# Microbrute_Output_Board.net
KiCad netlist of a schematic drawn in EAGLE
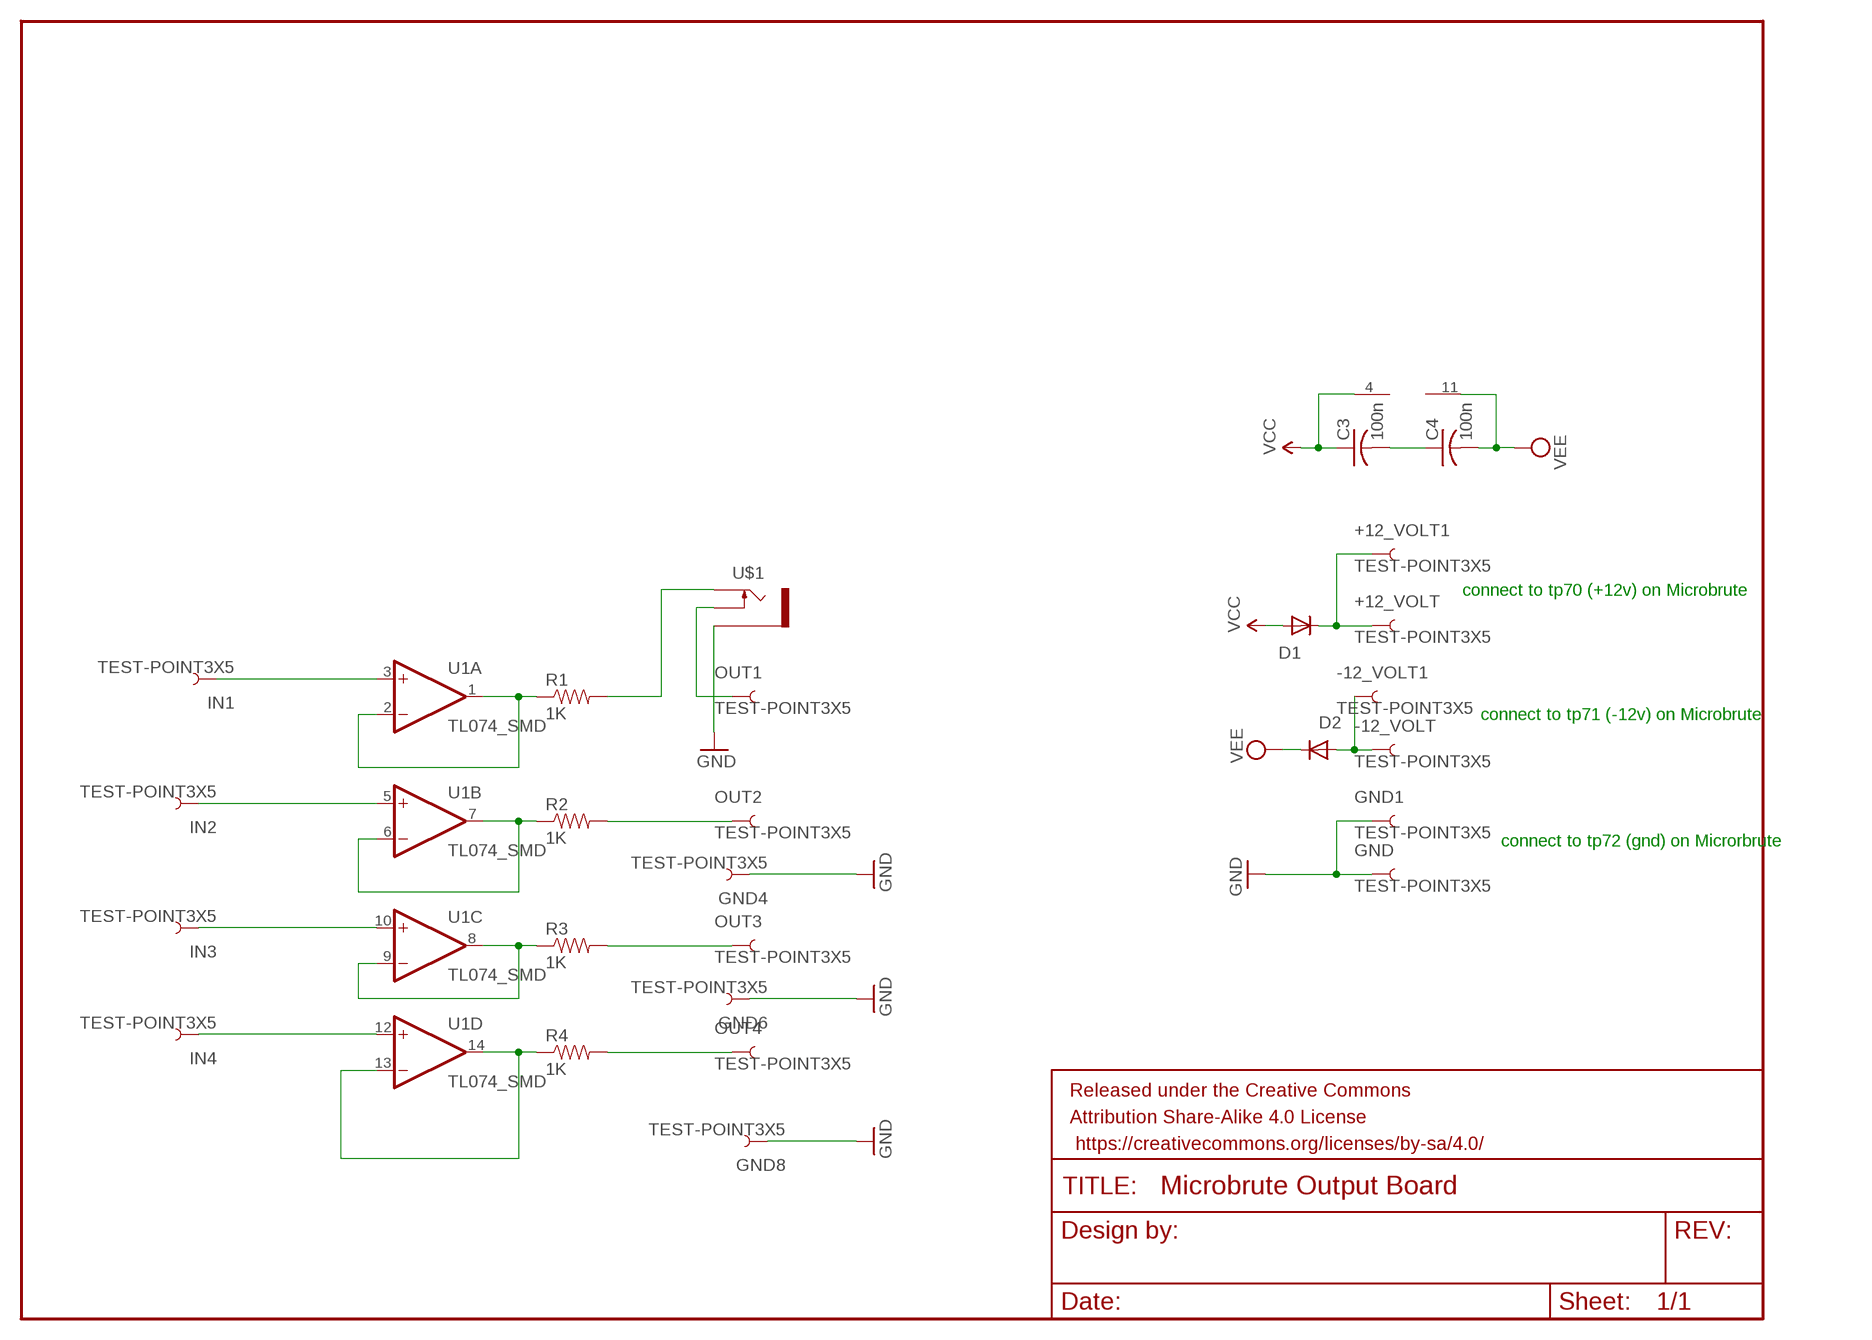
[diagram p0: schematic, sheet 1]

(export (version "E")
  (design (tool "Eeschema 10.0.6"))
  (components
    (comp (ref "+12_VOLT")
      (value "TEST-POINT3X5")
      (footprint "eagle-import:PAD.03X.05")
      (libsource (lib "eagle-import") (part "TEST-POINT3X5"))
    )
    (comp (ref "+12_VOLT1")
      (value "TEST-POINT3X5")
      (footprint "eagle-import:PAD.03X.05")
      (libsource (lib "eagle-import") (part "TEST-POINT3X5"))
    )
    (comp (ref "-12_VOLT")
      (value "TEST-POINT3X5")
      (footprint "eagle-import:PAD.03X.05")
      (libsource (lib "eagle-import") (part "TEST-POINT3X5"))
    )
    (comp (ref "-12_VOLT1")
      (value "TEST-POINT3X5")
      (footprint "eagle-import:PAD.03X.05")
      (libsource (lib "eagle-import") (part "TEST-POINT3X5"))
    )
    (comp (ref "C3")
      (value "100n")
      (footprint "eagle-import:C0603")
      (libsource (lib "eagle-import") (part "C-USC0603"))
    )
    (comp (ref "C4")
      (value "100n")
      (footprint "eagle-import:C0603")
      (libsource (lib "eagle-import") (part "C-USC0603"))
    )
    (comp (ref "D1")
      (value "1N5819HW")
      (footprint "eagle-import:SOD123")
      (libsource (lib "eagle-import") (part "DIODE-SOD123"))
    )
    (comp (ref "D2")
      (value "1N5819HW")
      (footprint "eagle-import:SOD123")
      (libsource (lib "eagle-import") (part "DIODE-SOD123"))
    )
    (comp (ref "FRAME1")
      (value "FRAME-LETTER")
      (footprint "eagle-import:CREATIVE_COMMONS")
      (libsource (lib "eagle-import") (part "FRAME-LETTER"))
    )
    (comp (ref "GND")
      (value "TEST-POINT3X5")
      (footprint "eagle-import:PAD.03X.05")
      (libsource (lib "eagle-import") (part "TEST-POINT3X5"))
    )
    (comp (ref "GND1")
      (value "TEST-POINT3X5")
      (footprint "eagle-import:PAD.03X.05")
      (libsource (lib "eagle-import") (part "TEST-POINT3X5"))
    )
    (comp (ref "GND4")
      (value "TEST-POINT3X5")
      (footprint "eagle-import:PAD.03X.05")
      (libsource (lib "eagle-import") (part "TEST-POINT3X5"))
    )
    (comp (ref "GND6")
      (value "TEST-POINT3X5")
      (footprint "eagle-import:PAD.03X.05")
      (libsource (lib "eagle-import") (part "TEST-POINT3X5"))
    )
    (comp (ref "GND8")
      (value "TEST-POINT3X5")
      (footprint "eagle-import:PAD.03X.05")
      (libsource (lib "eagle-import") (part "TEST-POINT3X5"))
    )
    (comp (ref "IN1")
      (value "TEST-POINT3X5")
      (footprint "eagle-import:PAD.03X.05")
      (libsource (lib "eagle-import") (part "TEST-POINT3X5"))
    )
    (comp (ref "IN2")
      (value "TEST-POINT3X5")
      (footprint "eagle-import:PAD.03X.05")
      (libsource (lib "eagle-import") (part "TEST-POINT3X5"))
    )
    (comp (ref "IN3")
      (value "TEST-POINT3X5")
      (footprint "eagle-import:PAD.03X.05")
      (libsource (lib "eagle-import") (part "TEST-POINT3X5"))
    )
    (comp (ref "IN4")
      (value "TEST-POINT3X5")
      (footprint "eagle-import:PAD.03X.05")
      (libsource (lib "eagle-import") (part "TEST-POINT3X5"))
    )
    (comp (ref "OUT1")
      (value "TEST-POINT3X5")
      (footprint "eagle-import:PAD.03X.05")
      (libsource (lib "eagle-import") (part "TEST-POINT3X5"))
    )
    (comp (ref "OUT2")
      (value "TEST-POINT3X5")
      (footprint "eagle-import:PAD.03X.05")
      (libsource (lib "eagle-import") (part "TEST-POINT3X5"))
    )
    (comp (ref "OUT3")
      (value "TEST-POINT3X5")
      (footprint "eagle-import:PAD.03X.05")
      (libsource (lib "eagle-import") (part "TEST-POINT3X5"))
    )
    (comp (ref "OUT4")
      (value "TEST-POINT3X5")
      (footprint "eagle-import:PAD.03X.05")
      (libsource (lib "eagle-import") (part "TEST-POINT3X5"))
    )
    (comp (ref "R1")
      (value "1K")
      (footprint "eagle-import:0603-RES")
      (libsource (lib "eagle-import") (part "1KOHM-1/10W-1%(0603)"))
    )
    (comp (ref "R2")
      (value "1K")
      (footprint "eagle-import:0603-RES")
      (libsource (lib "eagle-import") (part "1KOHM-1/10W-1%(0603)"))
    )
    (comp (ref "R3")
      (value "1K")
      (footprint "eagle-import:0603-RES")
      (libsource (lib "eagle-import") (part "1KOHM-1/10W-1%(0603)"))
    )
    (comp (ref "R4")
      (value "1K")
      (footprint "eagle-import:0603-RES")
      (libsource (lib "eagle-import") (part "1KOHM-1/10W-1%(0603)"))
    )
    (comp (ref "U$1")
      (value "THONKICONNNEW")
      (footprint "eagle-import:WQP-PJ301M-12_JACK")
      (libsource (lib "eagle-import") (part "THONKICONNNEW"))
    )
    (comp (ref "U1")
      (value "TL074_SMD")
      (footprint "eagle-import:SO14")
      (libsource (lib "eagle-import") (part "TL074_SMD"))
    )
  )
  (nets
    (net (code "1") (name "GND") (class "Default")
      (node (ref "GND") (pin "P$1") (pinfunction "1_P$1") (pintype "bidirectional"))
      (node (ref "GND1") (pin "P$1") (pinfunction "1_P$1") (pintype "bidirectional"))
      (node (ref "GND4") (pin "P$1") (pinfunction "1_P$1") (pintype "bidirectional"))
      (node (ref "GND6") (pin "P$1") (pinfunction "1_P$1") (pintype "bidirectional"))
      (node (ref "GND8") (pin "P$1") (pinfunction "1_P$1") (pintype "bidirectional"))
      (node (ref "U$1") (pin "P$3_SLEEVE") (pinfunction "SLEEVE_P$3_SLEEVE") (pintype "passive"))
    )
    (net (code "2") (name "Net-(+12_VOLT-1)") (class "Default")
      (node (ref "+12_VOLT") (pin "P$1") (pinfunction "1_P$1") (pintype "bidirectional"))
      (node (ref "+12_VOLT1") (pin "P$1") (pinfunction "1_P$1") (pintype "bidirectional"))
      (node (ref "D1") (pin "C") (pinfunction "C_C") (pintype "passive"))
    )
    (net (code "3") (name "Net-(-12_VOLT-1)") (class "Default")
      (node (ref "-12_VOLT") (pin "P$1") (pinfunction "1_P$1") (pintype "bidirectional"))
      (node (ref "-12_VOLT1") (pin "P$1") (pinfunction "1_P$1") (pintype "bidirectional"))
      (node (ref "D2") (pin "A") (pinfunction "A_A") (pintype "passive"))
    )
    (net (code "4") (name "Net-(C3-Pad2)") (class "Default")
      (node (ref "C3") (pin "2") (pinfunction "2_2") (pintype "passive"))
      (node (ref "C4") (pin "1") (pinfunction "1_1") (pintype "passive"))
    )
    (net (code "5") (name "Net-(IN1-1)") (class "Default")
      (node (ref "IN1") (pin "P$1") (pinfunction "1_P$1") (pintype "bidirectional"))
      (node (ref "U1") (pin "3") (pinfunction "+IN_3") (pintype "input"))
    )
    (net (code "6") (name "Net-(IN2-1)") (class "Default")
      (node (ref "IN2") (pin "P$1") (pinfunction "1_P$1") (pintype "bidirectional"))
      (node (ref "U1") (pin "5") (pinfunction "+IN_5") (pintype "input"))
    )
    (net (code "7") (name "Net-(IN3-1)") (class "Default")
      (node (ref "IN3") (pin "P$1") (pinfunction "1_P$1") (pintype "bidirectional"))
      (node (ref "U1") (pin "10") (pinfunction "+IN_10") (pintype "input"))
    )
    (net (code "8") (name "Net-(IN4-1)") (class "Default")
      (node (ref "IN4") (pin "P$1") (pinfunction "1_P$1") (pintype "bidirectional"))
      (node (ref "U1") (pin "12") (pinfunction "+IN_12") (pintype "input"))
    )
    (net (code "9") (name "Net-(OUT1-1)") (class "Default")
      (node (ref "OUT1") (pin "P$1") (pinfunction "1_P$1") (pintype "bidirectional"))
      (node (ref "U$1") (pin "P$2_SWITCH") (pinfunction "SWITCH_P$2_SWITCH") (pintype "passive"))
    )
    (net (code "10") (name "Net-(OUT2-1)") (class "Default")
      (node (ref "OUT2") (pin "P$1") (pinfunction "1_P$1") (pintype "bidirectional"))
      (node (ref "R2") (pin "2") (pinfunction "2_2") (pintype "passive"))
    )
    (net (code "11") (name "Net-(OUT3-1)") (class "Default")
      (node (ref "OUT3") (pin "P$1") (pinfunction "1_P$1") (pintype "bidirectional"))
      (node (ref "R3") (pin "2") (pinfunction "2_2") (pintype "passive"))
    )
    (net (code "12") (name "Net-(OUT4-1)") (class "Default")
      (node (ref "OUT4") (pin "P$1") (pinfunction "1_P$1") (pintype "bidirectional"))
      (node (ref "R4") (pin "2") (pinfunction "2_2") (pintype "passive"))
    )
    (net (code "13") (name "Net-(U$1-TIP)") (class "Default")
      (node (ref "R1") (pin "2") (pinfunction "2_2") (pintype "passive"))
      (node (ref "U$1") (pin "P$1_TIP") (pinfunction "TIP_P$1_TIP") (pintype "passive"))
    )
    (net (code "14") (name "Net-(U1A--IN)") (class "Default")
      (node (ref "R1") (pin "1") (pinfunction "1_1") (pintype "passive"))
      (node (ref "U1") (pin "1") (pinfunction "OUT_1") (pintype "output"))
      (node (ref "U1") (pin "2") (pinfunction "-IN_2") (pintype "input"))
    )
    (net (code "15") (name "Net-(U1B--IN)") (class "Default")
      (node (ref "R2") (pin "1") (pinfunction "1_1") (pintype "passive"))
      (node (ref "U1") (pin "6") (pinfunction "-IN_6") (pintype "input"))
      (node (ref "U1") (pin "7") (pinfunction "OUT_7") (pintype "output"))
    )
    (net (code "16") (name "Net-(U1C--IN)") (class "Default")
      (node (ref "R3") (pin "1") (pinfunction "1_1") (pintype "passive"))
      (node (ref "U1") (pin "8") (pinfunction "OUT_8") (pintype "output"))
      (node (ref "U1") (pin "9") (pinfunction "-IN_9") (pintype "input"))
    )
    (net (code "17") (name "Net-(U1D--IN)") (class "Default")
      (node (ref "R4") (pin "1") (pinfunction "1_1") (pintype "passive"))
      (node (ref "U1") (pin "13") (pinfunction "-IN_13") (pintype "input"))
      (node (ref "U1") (pin "14") (pinfunction "OUT_14") (pintype "output"))
    )
    (net (code "18") (name "VCC") (class "Default")
      (node (ref "C3") (pin "1") (pinfunction "1_1") (pintype "passive"))
      (node (ref "D1") (pin "A") (pinfunction "A_A") (pintype "passive"))
      (node (ref "U1") (pin "4") (pinfunction "V+_4") (pintype "power_in"))
    )
    (net (code "19") (name "VEE") (class "Default")
      (node (ref "C4") (pin "2") (pinfunction "2_2") (pintype "passive"))
      (node (ref "D2") (pin "C") (pinfunction "C_C") (pintype "passive"))
      (node (ref "U1") (pin "11") (pinfunction "V-_11") (pintype "power_in"))
    )
  )
)
